# Channel.net
KiCad netlist of a schematic drawn in Altium Designer
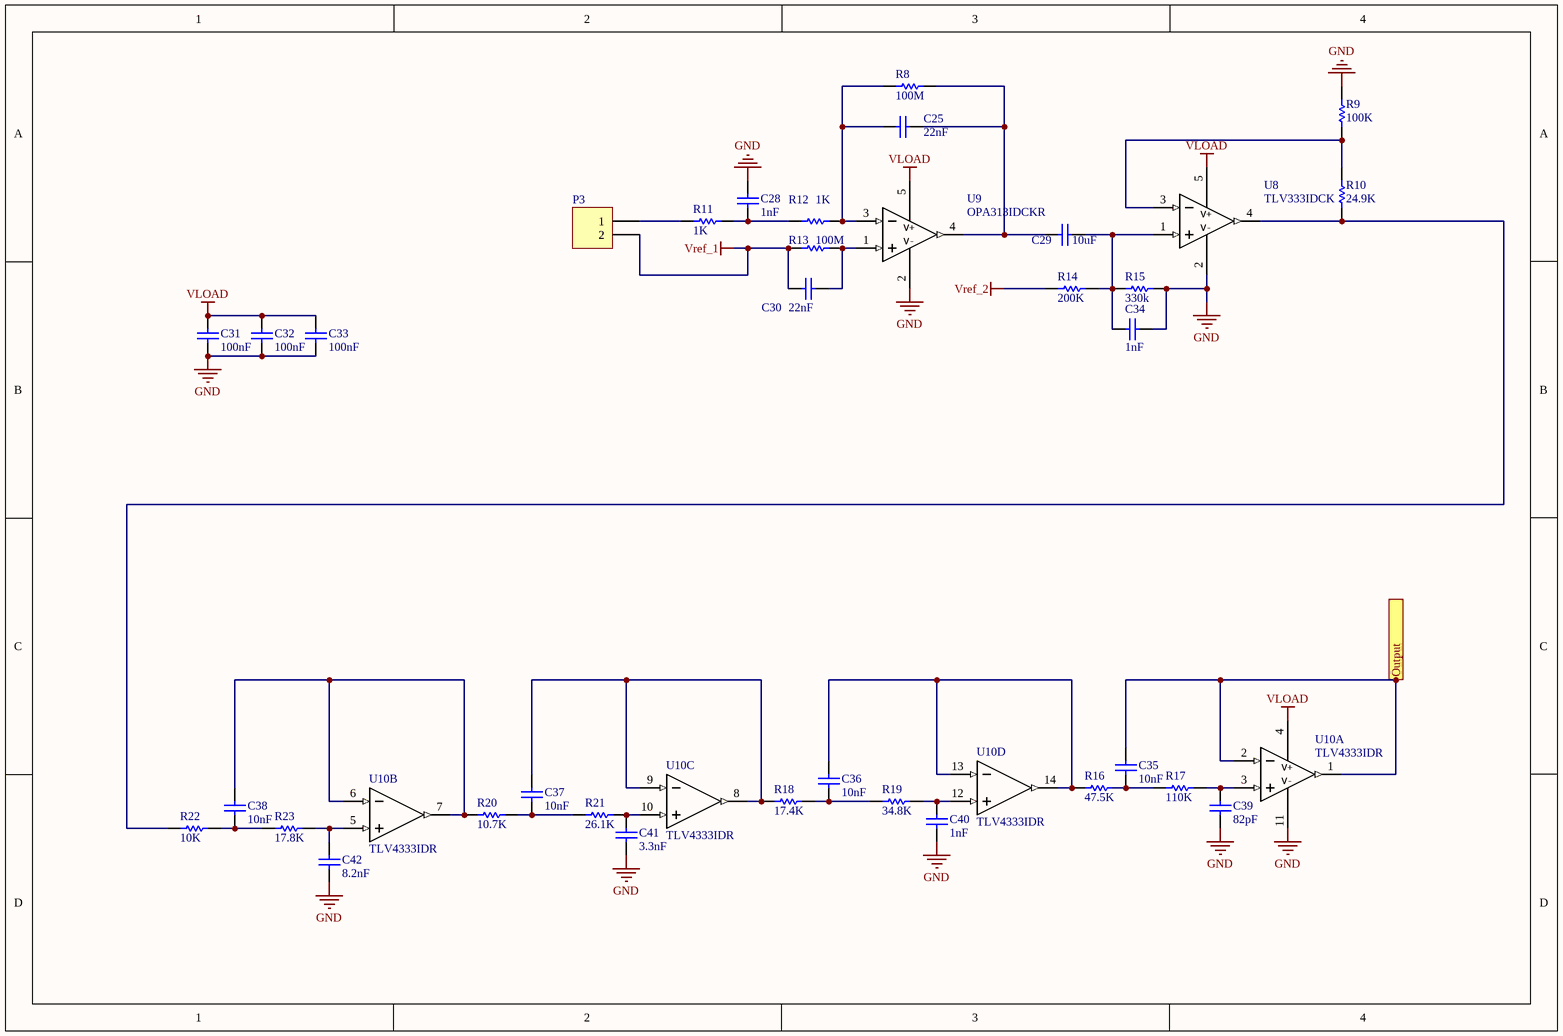
[diagram p0: Channel .SchDoc]

(export (version "E")
  (design (tool "Eeschema 10.0.6"))
  (components
    (comp (ref "C25")
      (value "22nF")
      (footprint "S0805C")
      (description "精度 ±5% \r\n容值 22nF \r\n额定电压 50V \r\n温漂系数（介质材料) C0G")
      (fields (field (name "MANUFACTURER") "TDK"))
      (libsource (lib "C") (part "22nF/0805/50V"))
    )
    (comp (ref "C28")
      (value "1nF")
      (footprint "S0603C")
      (description "精度 ±5% \r\n容值 1nF \r\n额定电压 50V \r\n温漂系数（介质材料) C0G")
      (fields (field (name "MANUFACTURER") "FH(风华)"))
      (libsource (lib "C") (part "1nF/0603/50V"))
    )
    (comp (ref "C29")
      (value "10uF")
      (footprint "S0805C")
      (description "精度 ±10% \r\n容值 10uF \r\n额定电压 16V \r\n温漂系数（介质材料) X7R")
      (fields (field (name "MANUFACTURER") "FH(风华)"))
      (libsource (lib "C") (part "10uF/0805/16V"))
    )
    (comp (ref "C30")
      (value "22nF")
      (footprint "S0805C")
      (description "精度 ±5% \r\n容值 22nF \r\n额定电压 50V \r\n温漂系数（介质材料) C0G")
      (fields (field (name "MANUFACTURER") "TDK"))
      (libsource (lib "C") (part "22nF/0805/50V"))
    )
    (comp (ref "C31")
      (value "100nF")
      (footprint "S0603C")
      (description "精度 ±10% \r\n容值 100nF \r\n额定电压 50V \r\n温漂系数（介质材料) X7R")
      (fields (field (name "MANUFACTURER") " FH(风华)"))
      (libsource (lib "C") (part "100nF/0603/50V"))
    )
    (comp (ref "C32")
      (value "100nF")
      (footprint "S0603C")
      (description "精度 ±10% \r\n容值 100nF \r\n额定电压 50V \r\n温漂系数（介质材料) X7R")
      (fields (field (name "MANUFACTURER") " FH(风华)"))
      (libsource (lib "C") (part "100nF/0603/50V"))
    )
    (comp (ref "C33")
      (value "100nF")
      (footprint "S0603C")
      (description "精度 ±10% \r\n容值 100nF \r\n额定电压 50V \r\n温漂系数（介质材料) X7R")
      (fields (field (name "MANUFACTURER") " FH(风华)"))
      (libsource (lib "C") (part "100nF/0603/50V"))
    )
    (comp (ref "C34")
      (value "1nF")
      (footprint "S0603C")
      (description "精度 ±5% \r\n容值 1nF \r\n额定电压 50V \r\n温漂系数（介质材料) C0G")
      (fields (field (name "MANUFACTURER") "FH(风华)"))
      (libsource (lib "C") (part "1nF/0603/50V"))
    )
    (comp (ref "C35")
      (value "10nF")
      (footprint "S0603C")
      (description "精度 ±5% \r\n容值 10nF \r\n额定电压 50V \r\n温漂系数（介质材料) C0G")
      (fields (field (name "MANUFACTURER") "FH(风华)"))
      (libsource (lib "C") (part "10nF/0603/C0G/50V"))
    )
    (comp (ref "C36")
      (value "10nF")
      (footprint "S0603C")
      (description "精度 ±5% \r\n容值 10nF \r\n额定电压 50V \r\n温漂系数（介质材料) C0G")
      (fields (field (name "MANUFACTURER") "FH(风华)"))
      (libsource (lib "C") (part "10nF/0603/C0G/50V"))
    )
    (comp (ref "C37")
      (value "10nF")
      (footprint "S0603C")
      (description "精度 ±5% \r\n容值 10nF \r\n额定电压 50V \r\n温漂系数（介质材料) C0G")
      (fields (field (name "MANUFACTURER") "FH(风华)"))
      (libsource (lib "C") (part "10nF/0603/C0G/50V"))
    )
    (comp (ref "C38")
      (value "10nF")
      (footprint "S0603C")
      (description "精度 ±5% \r\n容值 10nF \r\n额定电压 50V \r\n温漂系数（介质材料) C0G")
      (fields (field (name "MANUFACTURER") "FH(风华)"))
      (libsource (lib "C") (part "10nF/0603/C0G/50V"))
    )
    (comp (ref "C39")
      (value "82pF")
      (footprint "S0603C")
      (description "精度 ±5% \r\n容值 82pF \r\n额定电压 50V \r\n温漂系数（介质材料) C0G")
      (fields (field (name "MANUFACTURER") "FH(风华)"))
      (libsource (lib "C") (part "82pF/0603/C0G/50V"))
    )
    (comp (ref "C40")
      (value "1nF")
      (footprint "S0603C")
      (description "精度 ±5% \r\n容值 1nF \r\n额定电压 50V \r\n温漂系数（介质材料) C0G")
      (fields (field (name "MANUFACTURER") "FH(风华)"))
      (libsource (lib "C") (part "1nF/0603/50V"))
    )
    (comp (ref "C41")
      (value "3.3nF")
      (footprint "S0603C")
      (description "精度 ±5% \r\n容值 3.3nF \r\n额定电压 50V \r\n温漂系数（介质材料) C0G")
      (fields (field (name "MANUFACTURER") "FH(风华)"))
      (libsource (lib "C") (part "3.3nF/0603/50V"))
    )
    (comp (ref "C42")
      (value "8.2nF")
      (footprint "S0603C")
      (description "精度 ±5% \r\n容值 8.2nF \r\n额定电压 50V \r\n温漂系数（介质材料) C0G")
      (fields (field (name "MANUFACTURER") "TDK"))
      (libsource (lib "C") (part "8.2nF/0603/C0G"))
    )
    (comp (ref "P3")
      (value "Header 2")
      (footprint "CP1X2")
      (description "Header, 2-Pin")
      (libsource (lib "J") (part "Header 2"))
    )
    (comp (ref "R8")
      (value "100M")
      (footprint "S0805R")
      (description "精度 ±1% \r\n温度系数 ±100ppm/℃ \r\n功率 0.125W")
      (fields (field (name "MANUFACTURER") " UNI-ROYAL(厚声)"))
      (libsource (lib "R") (part "100M/0805"))
    )
    (comp (ref "R9")
      (value "100K")
      (footprint "S0603R")
      (description "精度 ±1% \r\n阻值 100kΩ \r\n温度系数 ±100ppm/℃ \r\n功率 0.1W")
      (fields (field (name "MANUFACTURER") " FH(风华)"))
      (libsource (lib "R") (part "100K/0603"))
    )
    (comp (ref "R10")
      (value "24.9K")
      (footprint "S0603R")
      (description "精度 ±1% \r\n温度系数 ±100ppm/℃ \r\n阻值 24.9kΩ \r\n功率 0.1W")
      (fields (field (name "MANUFACTURER") " FH(风华)"))
      (libsource (lib "R") (part "24.9K/0603"))
    )
    (comp (ref "R11")
      (value "1K")
      (footprint "S0603R")
      (description "精度 ±1% \r\n温度系数 ±100ppm/℃ \r\n阻值 1kΩ \r\n功率 0.1W")
      (fields (field (name "MANUFACTURER") " FH(风华)"))
      (libsource (lib "R") (part "1K/0603"))
    )
    (comp (ref "R12")
      (value "1K")
      (footprint "S0603R")
      (description "精度 ±1% \r\n温度系数 ±100ppm/℃ \r\n阻值 1kΩ \r\n功率 0.1W")
      (fields (field (name "MANUFACTURER") " FH(风华)"))
      (libsource (lib "R") (part "1K/0603"))
    )
    (comp (ref "R13")
      (value "100M")
      (footprint "S0805R")
      (description "精度 ±1% \r\n温度系数 ±100ppm/℃ \r\n功率 0.125W")
      (fields (field (name "MANUFACTURER") " UNI-ROYAL(厚声)"))
      (libsource (lib "R") (part "100M/0805"))
    )
    (comp (ref "R14")
      (value "200K")
      (footprint "S0603R")
      (description "精度 ±1% \r\n温度系数 ±100ppm/℃ \r\n功率 0.1W \r\n阻值 200kΩ")
      (fields (field (name "MANUFACTURER") " FH(风华)"))
      (libsource (lib "R") (part "200K/0603"))
    )
    (comp (ref "R15")
      (value "330k")
      (footprint "S0603R")
      (description "精度 ±1% \r\n温度系数 ±100ppm/℃ \r\n功率 0.1W")
      (fields (field (name "MANUFACTURER") " FH(风华)"))
      (libsource (lib "R") (part "330K/0603"))
    )
    (comp (ref "R16")
      (value "47.5K")
      (footprint "S0603R")
      (description "精度 ±1% \r\n阻值 47.5kΩ \r\n温度系数 ±100ppm/℃ \r\n功率 0.1W")
      (fields (field (name "MANUFACTURER") " FH(风华)"))
      (libsource (lib "R") (part "47.5K/0603"))
    )
    (comp (ref "R17")
      (value "110K")
      (footprint "S0603R")
      (description "精度 ±1% \r\n温度系数 ±100ppm/℃ \r\n功率 0.1W \r\n阻值 110kΩ")
      (fields (field (name "MANUFACTURER") " FH(风华)"))
      (libsource (lib "R") (part "110K/0603"))
    )
    (comp (ref "R18")
      (value "17.4K")
      (footprint "S0603R")
      (description "精度 ±1% \r\n温度系数 ±100ppm/℃ \r\n阻值 17.4kΩ \r\n功率 0.1W")
      (fields (field (name "MANUFACTURER") " FH(风华)"))
      (libsource (lib "R") (part "17.4K/0603"))
    )
    (comp (ref "R19")
      (value "34.8K")
      (footprint "S0603R")
      (description "精度 ±1% \r\n阻值 34.8kΩ \r\n温度系数 ±100ppm/℃ \r\n功率 0.1W")
      (fields (field (name "MANUFACTURER") " FH(风华)"))
      (libsource (lib "R") (part "34.8K/0603"))
    )
    (comp (ref "R20")
      (value "10.7K")
      (footprint "S0603R")
      (description "精度 ±1% \r\n温度系数 ±100ppm/℃ \r\n阻值 10.7kΩ \r\n功率 0.1W")
      (fields (field (name "MANUFACTURER") " FH(风华)"))
      (libsource (lib "R") (part "10.7K/0603"))
    )
    (comp (ref "R21")
      (value "26.1K")
      (footprint "S0603R")
      (description "精度 ±1% \r\n温度系数 ±100ppm/℃ \r\n功率 0.1W \r\n阻值 26.1kΩ")
      (fields (field (name "MANUFACTURER") " FH(风华)"))
      (libsource (lib "R") (part "26.1K/0603"))
    )
    (comp (ref "R22")
      (value "10K")
      (footprint "S0603R")
      (description "精度 ±1% \r\n温度系数 ±100ppm/℃ \r\n阻值 10kΩ \r\n功率 0.1W")
      (fields (field (name "MANUFACTURER") " FH(风华)"))
      (libsource (lib "R") (part "10K/0603"))
    )
    (comp (ref "R23")
      (value "17.8K")
      (footprint "S0603R")
      (description "精度 ±1% \r\n温度系数 ±100ppm/℃ \r\n功率 0.1W")
      (fields (field (name "MANUFACTURER") " FH(风华)"))
      (libsource (lib "R") (part "17.8K/0603"))
    )
    (comp (ref "U8")
      (value "TLV333IDCK")
      (footprint "DCK0005A_N")
      (description "电源电压 1.8V ~ 5.5V, ±0.9V ~ 2.75V\r\n增益带宽积（GBP） 350kHz \r\n压摆率（SR） 0.16 V/us \r\n工作温度 -40°C ~ 125°C")
      (fields (field (name "MANUFACTURER") "TI(德州仪器)"))
      (libsource (lib "OP") (part "TLV333IDCK"))
    )
    (comp (ref "U9")
      (value "OPA313IDCKR")
      (footprint "DCK0005A_N")
      (fields (field (name "MANUFACTURER") "TI(德州仪器)"))
      (libsource (lib "OP") (part "OPA313IDCKR"))
    )
    (comp (ref "U10")
      (value "TLV4333IDR")
      (footprint "D14")
      (description "电源电压 1.8V ~ 5.5V, ±0.9V ~ 2.75V\r\n增益带宽积（GBP） 350kHz \r\n压摆率（SR） 0.16 V/us \r\n工作温度 -40°C ~ 125°C")
      (fields (field (name "MANUFACTURER") "TI(德州仪器)"))
      (libsource (lib "OP") (part "TLV4333IDR"))
    )
  )
  (nets
    (net (code "1") (name "/Output") (class "Default")
      (node (ref "C35") (pin "2") (pinfunction "2_2") (pintype "passive"))
      (node (ref "U10") (pin "1") (pinfunction "OUT_1") (pintype "output"))
      (node (ref "U10") (pin "2") (pinfunction "IN-_2") (pintype "input"))
    )
    (net (code "2") (name "GND") (class "Default")
      (node (ref "C28") (pin "2") (pinfunction "2_2") (pintype "passive"))
      (node (ref "C31") (pin "2") (pinfunction "2_2") (pintype "passive"))
      (node (ref "C32") (pin "2") (pinfunction "2_2") (pintype "passive"))
      (node (ref "C33") (pin "2") (pinfunction "2_2") (pintype "passive"))
      (node (ref "C34") (pin "1") (pinfunction "1_1") (pintype "passive"))
      (node (ref "C39") (pin "1") (pinfunction "1_1") (pintype "passive"))
      (node (ref "C40") (pin "2") (pinfunction "2_2") (pintype "passive"))
      (node (ref "C41") (pin "1") (pinfunction "1_1") (pintype "passive"))
      (node (ref "C42") (pin "1") (pinfunction "1_1") (pintype "passive"))
      (node (ref "R15") (pin "2") (pinfunction "2_2") (pintype "passive"))
      (node (ref "R9") (pin "2") (pinfunction "2_2") (pintype "passive"))
      (node (ref "U10") (pin "11") (pinfunction "V-_11") (pintype "power_in"))
      (node (ref "U8") (pin "2") (pinfunction "V-_2") (pintype "power_in"))
      (node (ref "U9") (pin "2") (pinfunction "V-_2") (pintype "power_in"))
    )
    (net (code "3") (name "Net-(C28-Pad1)") (class "Default")
      (node (ref "C28") (pin "1") (pinfunction "1_1") (pintype "passive"))
      (node (ref "R11") (pin "2") (pinfunction "2_2") (pintype "passive"))
      (node (ref "R12") (pin "1") (pinfunction "1_1") (pintype "passive"))
    )
    (net (code "4") (name "Net-(C35-Pad1)") (class "Default")
      (node (ref "C35") (pin "1") (pinfunction "1_1") (pintype "passive"))
      (node (ref "R16") (pin "2") (pinfunction "2_2") (pintype "passive"))
      (node (ref "R17") (pin "1") (pinfunction "1_1") (pintype "passive"))
    )
    (net (code "5") (name "Net-(C36-Pad1)") (class "Default")
      (node (ref "C36") (pin "1") (pinfunction "1_1") (pintype "passive"))
      (node (ref "R18") (pin "2") (pinfunction "2_2") (pintype "passive"))
      (node (ref "R19") (pin "1") (pinfunction "1_1") (pintype "passive"))
    )
    (net (code "6") (name "Net-(C37-Pad1)") (class "Default")
      (node (ref "C37") (pin "1") (pinfunction "1_1") (pintype "passive"))
      (node (ref "R20") (pin "2") (pinfunction "2_2") (pintype "passive"))
      (node (ref "R21") (pin "1") (pinfunction "1_1") (pintype "passive"))
    )
    (net (code "7") (name "Net-(C38-Pad1)") (class "Default")
      (node (ref "C38") (pin "1") (pinfunction "1_1") (pintype "passive"))
      (node (ref "R22") (pin "2") (pinfunction "2_2") (pintype "passive"))
      (node (ref "R23") (pin "1") (pinfunction "1_1") (pintype "passive"))
    )
    (net (code "8") (name "Net-(P3-Pad1)") (class "Default")
      (node (ref "P3") (pin "1") (pinfunction "1_1") (pintype "passive"))
      (node (ref "R11") (pin "1") (pinfunction "1_1") (pintype "passive"))
    )
    (net (code "9") (name "Net-(U8-IN+)") (class "Default")
      (node (ref "C29") (pin "1") (pinfunction "1_1") (pintype "passive"))
      (node (ref "C34") (pin "2") (pinfunction "2_2") (pintype "passive"))
      (node (ref "R14") (pin "2") (pinfunction "2_2") (pintype "passive"))
      (node (ref "R15") (pin "1") (pinfunction "1_1") (pintype "passive"))
      (node (ref "U8") (pin "1") (pinfunction "IN+_1") (pintype "input"))
    )
    (net (code "10") (name "Net-(U8-IN-)") (class "Default")
      (node (ref "R10") (pin "2") (pinfunction "2_2") (pintype "passive"))
      (node (ref "R9") (pin "1") (pinfunction "1_1") (pintype "passive"))
      (node (ref "U8") (pin "3") (pinfunction "IN-_3") (pintype "input"))
    )
    (net (code "11") (name "Net-(U8-OUT)") (class "Default")
      (node (ref "R10") (pin "1") (pinfunction "1_1") (pintype "passive"))
      (node (ref "R22") (pin "1") (pinfunction "1_1") (pintype "passive"))
      (node (ref "U8") (pin "4") (pinfunction "OUT_4") (pintype "output"))
    )
    (net (code "12") (name "Net-(U9-IN+)") (class "Default")
      (node (ref "C30") (pin "1") (pinfunction "1_1") (pintype "passive"))
      (node (ref "R13") (pin "2") (pinfunction "2_2") (pintype "passive"))
      (node (ref "U9") (pin "1") (pinfunction "IN+_1") (pintype "input"))
    )
    (net (code "13") (name "Net-(U9-IN-)") (class "Default")
      (node (ref "C25") (pin "2") (pinfunction "2_2") (pintype "passive"))
      (node (ref "R12") (pin "2") (pinfunction "2_2") (pintype "passive"))
      (node (ref "R8") (pin "1") (pinfunction "1_1") (pintype "passive"))
      (node (ref "U9") (pin "3") (pinfunction "IN-_3") (pintype "input"))
    )
    (net (code "14") (name "Net-(U9-OUT)") (class "Default")
      (node (ref "C25") (pin "1") (pinfunction "1_1") (pintype "passive"))
      (node (ref "C29") (pin "2") (pinfunction "2_2") (pintype "passive"))
      (node (ref "R8") (pin "2") (pinfunction "2_2") (pintype "passive"))
      (node (ref "U9") (pin "4") (pinfunction "OUT_4") (pintype "output"))
    )
    (net (code "15") (name "Net-(U10A-IN+)") (class "Default")
      (node (ref "C39") (pin "2") (pinfunction "2_2") (pintype "passive"))
      (node (ref "R17") (pin "2") (pinfunction "2_2") (pintype "passive"))
      (node (ref "U10") (pin "3") (pinfunction "IN+_3") (pintype "input"))
    )
    (net (code "16") (name "Net-(U10B-IN+)") (class "Default")
      (node (ref "C42") (pin "2") (pinfunction "2_2") (pintype "passive"))
      (node (ref "R23") (pin "2") (pinfunction "2_2") (pintype "passive"))
      (node (ref "U10") (pin "5") (pinfunction "IN+_5") (pintype "input"))
    )
    (net (code "17") (name "Net-(U10B-IN-)") (class "Default")
      (node (ref "C38") (pin "2") (pinfunction "2_2") (pintype "passive"))
      (node (ref "R20") (pin "1") (pinfunction "1_1") (pintype "passive"))
      (node (ref "U10") (pin "6") (pinfunction "IN-_6") (pintype "input"))
      (node (ref "U10") (pin "7") (pinfunction "OUT_7") (pintype "output"))
    )
    (net (code "18") (name "Net-(U10C-IN+)") (class "Default")
      (node (ref "C41") (pin "2") (pinfunction "2_2") (pintype "passive"))
      (node (ref "R21") (pin "2") (pinfunction "2_2") (pintype "passive"))
      (node (ref "U10") (pin "10") (pinfunction "IN+_10") (pintype "input"))
    )
    (net (code "19") (name "Net-(U10C-IN-)") (class "Default")
      (node (ref "C37") (pin "2") (pinfunction "2_2") (pintype "passive"))
      (node (ref "R18") (pin "1") (pinfunction "1_1") (pintype "passive"))
      (node (ref "U10") (pin "8") (pinfunction "OUT_8") (pintype "output"))
      (node (ref "U10") (pin "9") (pinfunction "IN-_9") (pintype "input"))
    )
    (net (code "20") (name "Net-(U10D-IN+)") (class "Default")
      (node (ref "C40") (pin "1") (pinfunction "1_1") (pintype "passive"))
      (node (ref "R19") (pin "2") (pinfunction "2_2") (pintype "passive"))
      (node (ref "U10") (pin "12") (pinfunction "IN+_12") (pintype "input"))
    )
    (net (code "21") (name "Net-(U10D-IN-)") (class "Default")
      (node (ref "C36") (pin "2") (pinfunction "2_2") (pintype "passive"))
      (node (ref "R16") (pin "1") (pinfunction "1_1") (pintype "passive"))
      (node (ref "U10") (pin "13") (pinfunction "IN-_13") (pintype "input"))
      (node (ref "U10") (pin "14") (pinfunction "OUT_14") (pintype "output"))
    )
    (net (code "22") (name "VLOAD") (class "Default")
      (node (ref "C31") (pin "1") (pinfunction "1_1") (pintype "passive"))
      (node (ref "C32") (pin "1") (pinfunction "1_1") (pintype "passive"))
      (node (ref "C33") (pin "1") (pinfunction "1_1") (pintype "passive"))
      (node (ref "U10") (pin "4") (pinfunction "V+_4") (pintype "power_in"))
      (node (ref "U8") (pin "5") (pinfunction "V+_5") (pintype "power_in"))
      (node (ref "U9") (pin "5") (pinfunction "V+_5") (pintype "power_in"))
    )
    (net (code "23") (name "Vref_1") (class "Default")
      (node (ref "C30") (pin "2") (pinfunction "2_2") (pintype "passive"))
      (node (ref "P3") (pin "2") (pinfunction "2_2") (pintype "passive"))
      (node (ref "R13") (pin "1") (pinfunction "1_1") (pintype "passive"))
    )
    (net (code "24") (name "Vref_2") (class "Default")
      (node (ref "R14") (pin "1") (pinfunction "1_1") (pintype "passive"))
    )
  )
)
